# SCH_VELOS-R1_2025-07-28.net
KiCad netlist of a schematic drawn in EasyEDA
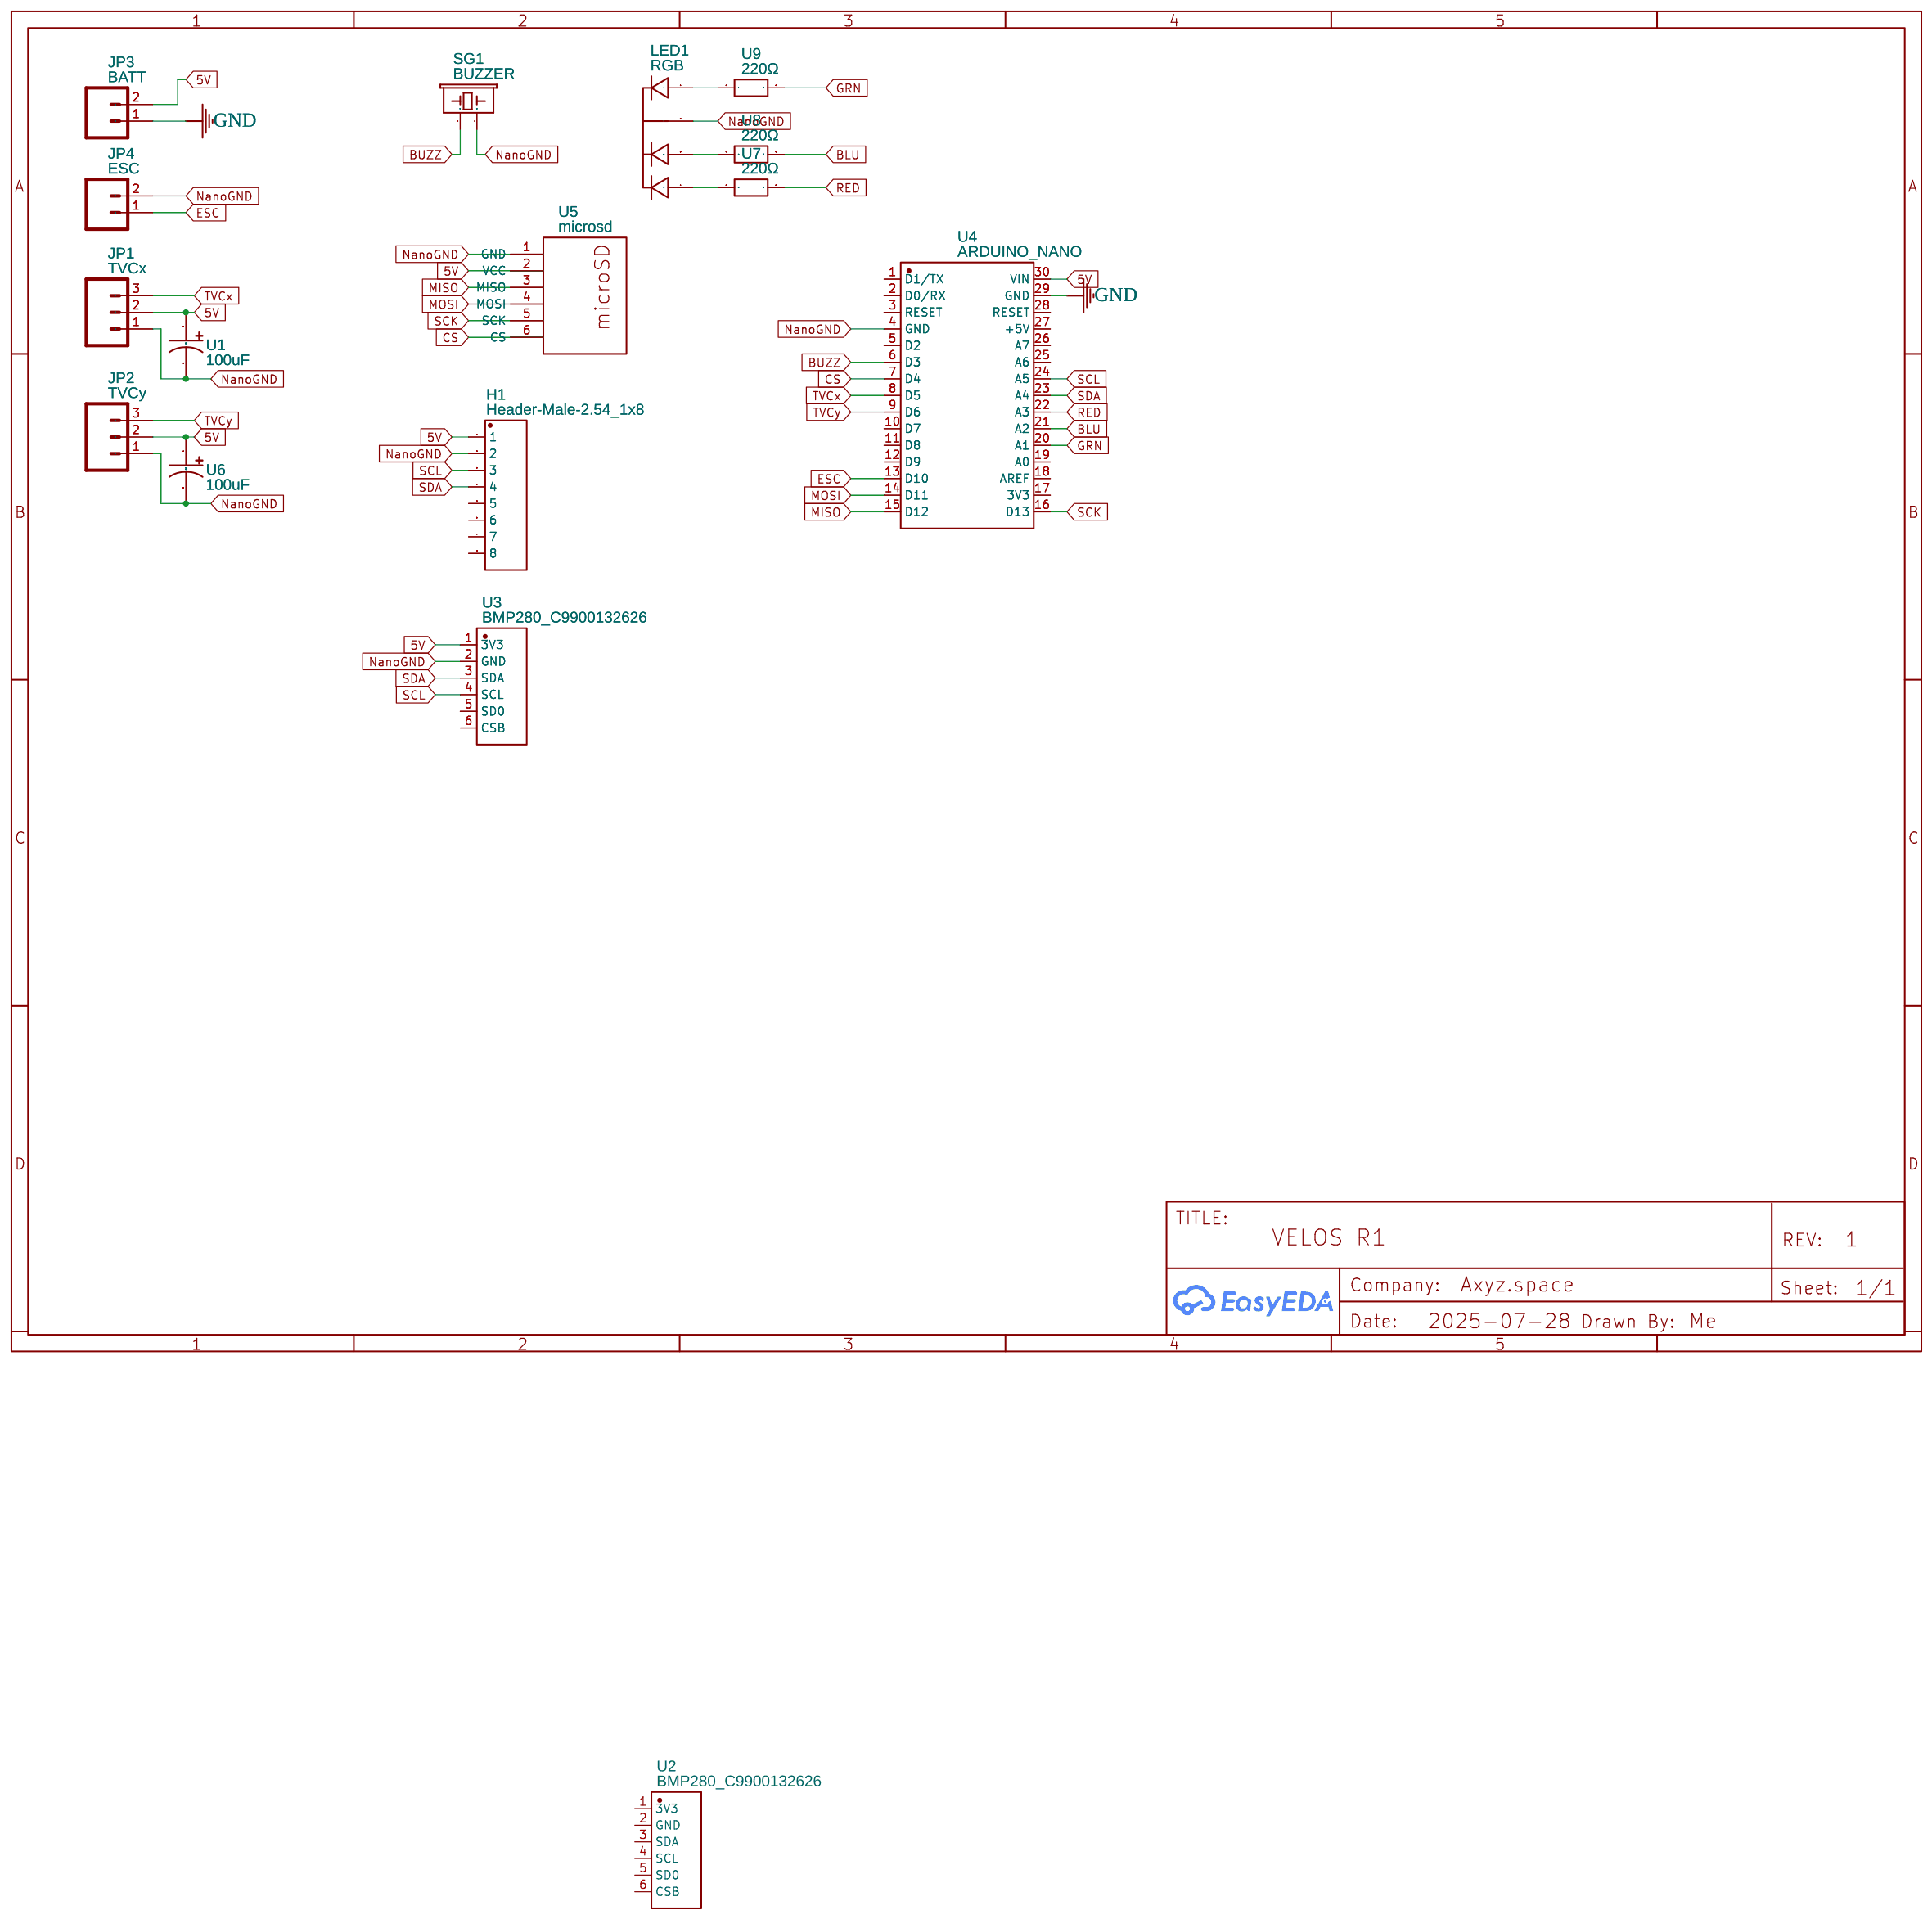
[diagram p0: schematic sheet]

(export (version "E")
  (design (tool "Eeschema 10.0.6"))
  (components
    (comp (ref "H1")
      (value "Header-Male-2.54_1x8")
      (fields (field (name "Manufacturer Part") "B-2100S08P-A110") (field (name "Manufacturer") "Ckmtw(灿科盟)"))
      (libsource (lib "") (part "Header-Male-2.54_1x8"))
    )
    (comp (ref "JP1") (value "TVCx") (libsource (lib "") (part "M03-SCREW-5MM")))
    (comp (ref "JP2") (value "TVCy") (libsource (lib "") (part "M03-SCREW-5MM")))
    (comp (ref "JP3") (value "BATT") (libsource (lib "") (part "M023.5MM")))
    (comp (ref "JP4") (value "ESC") (libsource (lib "") (part "M023.5MM")))
    (comp (ref "LED1")
      (value "RGB")
      (fields
        (field (name "Manufacturer Part") "TJ-L5FYTXHMCSLCRGB-A5")
        (field (name "Manufacturer") "TOGIALED(统佳)")
      )
      (libsource (lib "") (part "TJ-L5FYTXHMCSLCRGB-A5"))
    )
    (comp (ref "SG1") (value "BUZZER") (libsource (lib "") (part "BUZZER")))
    (comp (ref "U1")
      (value "100uF")
      (fields
        (field (name "Manufacturer Part") "35ZLH100MHFC(6.3X11)")
        (field (name "Manufacturer") "rubycon(红宝石)")
      )
      (libsource (lib "") (part "35ZLH100MHFC(6.3X11)"))
    )
    (comp (ref "U2")
      (value "BMP280_C9900132626")
      (fields (field (name "Manufacturer Part") "BMP280"))
      (libsource (lib "") (part "BMP280_C9900132626"))
    )
    (comp (ref "U3")
      (value "BMP280_C9900132626")
      (fields (field (name "Manufacturer Part") "BMP280"))
      (libsource (lib "") (part "BMP280_C9900132626"))
    )
    (comp (ref "U4") (value "ARDUINO_NANO") (libsource (lib "") (part "ARDUINO_NANO")))
    (comp (ref "U5") (value "microsd") (libsource (lib "") (part "microsd")))
    (comp (ref "U6")
      (value "100uF")
      (fields
        (field (name "Manufacturer Part") "35ZLH100MHFC(6.3X11)")
        (field (name "Manufacturer") "rubycon(红宝石)")
      )
      (libsource (lib "") (part "35ZLH100MHFC(6.3X11)"))
    )
    (comp (ref "U7")
      (value "220Ω")
      (fields
        (field (name "Manufacturer Part") "MBE04140C2200FC100")
        (field (name "Manufacturer") "VISHAY(威世)")
      )
      (libsource (lib "") (part "MBE04140C2200FC100"))
    )
    (comp (ref "U8")
      (value "220Ω")
      (fields
        (field (name "Manufacturer Part") "MBE04140C2200FC100")
        (field (name "Manufacturer") "VISHAY(威世)")
      )
      (libsource (lib "") (part "MBE04140C2200FC100"))
    )
    (comp (ref "U9")
      (value "220Ω")
      (fields
        (field (name "Manufacturer Part") "MBE04140C2200FC100")
        (field (name "Manufacturer") "VISHAY(威世)")
      )
      (libsource (lib "") (part "MBE04140C2200FC100"))
    )
  )
  (nets
    (net (code "1") (name "5V") (class "Default")
      (node (ref "H1") (pin "1") (pinfunction "1_1") (pintype "unspecified"))
      (node (ref "JP1") (pin "2") (pinfunction "2_2") (pintype "unspecified"))
      (node (ref "JP2") (pin "2") (pinfunction "2_2") (pintype "unspecified"))
      (node (ref "JP3") (pin "2") (pinfunction "2_2") (pintype "unspecified"))
      (node (ref "U1") (pin "1") (pinfunction "1_1") (pintype "unspecified"))
      (node (ref "U3") (pin "1") (pinfunction "3V3_1") (pintype "unspecified"))
      (node (ref "U4") (pin "30") (pinfunction "VIN_30") (pintype "unspecified"))
      (node (ref "U5") (pin "2") (pinfunction "VCC_2") (pintype "unspecified"))
      (node (ref "U6") (pin "1") (pinfunction "1_1") (pintype "unspecified"))
    )
    (net (code "2") (name "BLU") (class "Default")
      (node (ref "U4") (pin "21") (pinfunction "A2_21") (pintype "unspecified"))
      (node (ref "U8") (pin "2") (pinfunction "2_2") (pintype "unspecified"))
    )
    (net (code "3") (name "BUZZ") (class "Default")
      (node (ref "SG1") (pin "+") (pinfunction "1_+") (pintype "unspecified"))
      (node (ref "U4") (pin "6") (pinfunction "D3_6") (pintype "unspecified"))
    )
    (net (code "4") (name "CS") (class "Default")
      (node (ref "U4") (pin "7") (pinfunction "D4_7") (pintype "unspecified"))
      (node (ref "U5") (pin "6") (pinfunction "CS_6") (pintype "unspecified"))
    )
    (net (code "5") (name "ESC") (class "Default")
      (node (ref "JP4") (pin "1") (pinfunction "1_1") (pintype "unspecified"))
      (node (ref "U4") (pin "13") (pinfunction "D10_13") (pintype "unspecified"))
    )
    (net (code "6") (name "GND") (class "Default")
      (node (ref "JP3") (pin "1") (pinfunction "1_1") (pintype "unspecified"))
      (node (ref "U4") (pin "29") (pinfunction "GND_29") (pintype "unspecified"))
    )
    (net (code "7") (name "GRN") (class "Default")
      (node (ref "U4") (pin "20") (pinfunction "A1_20") (pintype "unspecified"))
      (node (ref "U9") (pin "2") (pinfunction "2_2") (pintype "unspecified"))
    )
    (net (code "8") (name "MISO") (class "Default")
      (node (ref "U4") (pin "15") (pinfunction "D12_15") (pintype "unspecified"))
      (node (ref "U5") (pin "3") (pinfunction "MISO_3") (pintype "unspecified"))
    )
    (net (code "9") (name "MOSI") (class "Default")
      (node (ref "U4") (pin "14") (pinfunction "D11_14") (pintype "unspecified"))
      (node (ref "U5") (pin "4") (pinfunction "MOSI_4") (pintype "unspecified"))
    )
    (net (code "10") (name "NanoGND") (class "Default")
      (node (ref "H1") (pin "2") (pinfunction "2_2") (pintype "unspecified"))
      (node (ref "JP1") (pin "1") (pinfunction "1_1") (pintype "unspecified"))
      (node (ref "JP2") (pin "1") (pinfunction "1_1") (pintype "unspecified"))
      (node (ref "JP4") (pin "2") (pinfunction "2_2") (pintype "unspecified"))
      (node (ref "LED1") (pin "2") (pinfunction "-_2") (pintype "unspecified"))
      (node (ref "SG1") (pin "-") (pinfunction "2_-") (pintype "unspecified"))
      (node (ref "U1") (pin "2") (pinfunction "2_2") (pintype "unspecified"))
      (node (ref "U3") (pin "2") (pinfunction "GND_2") (pintype "unspecified"))
      (node (ref "U4") (pin "4") (pinfunction "GND_4") (pintype "unspecified"))
      (node (ref "U5") (pin "1") (pinfunction "GND_1") (pintype "unspecified"))
      (node (ref "U6") (pin "2") (pinfunction "2_2") (pintype "unspecified"))
    )
    (net (code "11") (name "Net-(LED1-Pad1)") (class "Default")
      (node (ref "LED1") (pin "1") (pinfunction "1_1") (pintype "unspecified"))
      (node (ref "U9") (pin "1") (pinfunction "1_1") (pintype "unspecified"))
    )
    (net (code "12") (name "Net-(LED1-Pad3)") (class "Default")
      (node (ref "LED1") (pin "3") (pinfunction "3_3") (pintype "unspecified"))
      (node (ref "U8") (pin "1") (pinfunction "1_1") (pintype "unspecified"))
    )
    (net (code "13") (name "Net-(LED1-Pad4)") (class "Default")
      (node (ref "LED1") (pin "4") (pinfunction "4_4") (pintype "unspecified"))
      (node (ref "U7") (pin "1") (pinfunction "1_1") (pintype "unspecified"))
    )
    (net (code "14") (name "RED") (class "Default")
      (node (ref "U4") (pin "22") (pinfunction "A3_22") (pintype "unspecified"))
      (node (ref "U7") (pin "2") (pinfunction "2_2") (pintype "unspecified"))
    )
    (net (code "15") (name "SCK") (class "Default")
      (node (ref "U4") (pin "16") (pinfunction "D13_16") (pintype "unspecified"))
      (node (ref "U5") (pin "5") (pinfunction "SCK_5") (pintype "unspecified"))
    )
    (net (code "16") (name "SCL") (class "Default")
      (node (ref "H1") (pin "3") (pinfunction "3_3") (pintype "unspecified"))
      (node (ref "U3") (pin "4") (pinfunction "SCL_4") (pintype "unspecified"))
      (node (ref "U4") (pin "24") (pinfunction "A5_24") (pintype "unspecified"))
    )
    (net (code "17") (name "SDA") (class "Default")
      (node (ref "H1") (pin "4") (pinfunction "4_4") (pintype "unspecified"))
      (node (ref "U3") (pin "3") (pinfunction "SDA_3") (pintype "unspecified"))
      (node (ref "U4") (pin "23") (pinfunction "A4_23") (pintype "unspecified"))
    )
    (net (code "18") (name "TVCx") (class "Default")
      (node (ref "JP1") (pin "3") (pinfunction "3_3") (pintype "unspecified"))
      (node (ref "U4") (pin "8") (pinfunction "D5_8") (pintype "unspecified"))
    )
    (net (code "19") (name "TVCy") (class "Default")
      (node (ref "JP2") (pin "3") (pinfunction "3_3") (pintype "unspecified"))
      (node (ref "U4") (pin "9") (pinfunction "D6_9") (pintype "unspecified"))
    )
    (net (code "20") (name "unconnected-(H1-Pad5)") (class "Default")
      (node (ref "H1") (pin "5") (pinfunction "5_5") (pintype "unspecified"))
    )
    (net (code "21") (name "unconnected-(H1-Pad6)") (class "Default")
      (node (ref "H1") (pin "6") (pinfunction "6_6") (pintype "unspecified"))
    )
    (net (code "22") (name "unconnected-(H1-Pad7)") (class "Default")
      (node (ref "H1") (pin "7") (pinfunction "7_7") (pintype "unspecified"))
    )
    (net (code "23") (name "unconnected-(H1-Pad8)") (class "Default")
      (node (ref "H1") (pin "8") (pinfunction "8_8") (pintype "unspecified"))
    )
    (net (code "24") (name "unconnected-(U2-3V3-Pad1)") (class "Default")
      (node (ref "U2") (pin "1") (pinfunction "3V3_1") (pintype "unspecified"))
    )
    (net (code "25") (name "unconnected-(U2-CSB-Pad6)") (class "Default")
      (node (ref "U2") (pin "6") (pinfunction "CSB_6") (pintype "unspecified"))
    )
    (net (code "26") (name "unconnected-(U2-GND-Pad2)") (class "Default")
      (node (ref "U2") (pin "2") (pinfunction "GND_2") (pintype "unspecified"))
    )
    (net (code "27") (name "unconnected-(U2-SCL-Pad4)") (class "Default")
      (node (ref "U2") (pin "4") (pinfunction "SCL_4") (pintype "unspecified"))
    )
    (net (code "28") (name "unconnected-(U2-SD0-Pad5)") (class "Default")
      (node (ref "U2") (pin "5") (pinfunction "SD0_5") (pintype "unspecified"))
    )
    (net (code "29") (name "unconnected-(U2-SDA-Pad3)") (class "Default")
      (node (ref "U2") (pin "3") (pinfunction "SDA_3") (pintype "unspecified"))
    )
    (net (code "30") (name "unconnected-(U3-CSB-Pad6)") (class "Default")
      (node (ref "U3") (pin "6") (pinfunction "CSB_6") (pintype "unspecified"))
    )
    (net (code "31") (name "unconnected-(U3-SD0-Pad5)") (class "Default")
      (node (ref "U3") (pin "5") (pinfunction "SD0_5") (pintype "unspecified"))
    )
    (net (code "32") (name "unconnected-(U4-+5V-Pad27)") (class "Default")
      (node (ref "U4") (pin "27") (pinfunction "+5V_27") (pintype "unspecified"))
    )
    (net (code "33") (name "unconnected-(U4-3V3-Pad17)") (class "Default")
      (node (ref "U4") (pin "17") (pinfunction "3V3_17") (pintype "unspecified"))
    )
    (net (code "34") (name "unconnected-(U4-A0-Pad19)") (class "Default")
      (node (ref "U4") (pin "19") (pinfunction "A0_19") (pintype "unspecified"))
    )
    (net (code "35") (name "unconnected-(U4-A6-Pad25)") (class "Default")
      (node (ref "U4") (pin "25") (pinfunction "A6_25") (pintype "unspecified"))
    )
    (net (code "36") (name "unconnected-(U4-A7-Pad26)") (class "Default")
      (node (ref "U4") (pin "26") (pinfunction "A7_26") (pintype "unspecified"))
    )
    (net (code "37") (name "unconnected-(U4-AREF-Pad18)") (class "Default")
      (node (ref "U4") (pin "18") (pinfunction "AREF_18") (pintype "unspecified"))
    )
    (net (code "38") (name "unconnected-(U4-D0{slash}RX-Pad2)") (class "Default")
      (node (ref "U4") (pin "2") (pinfunction "D0/RX_2") (pintype "unspecified"))
    )
    (net (code "39") (name "unconnected-(U4-D1{slash}TX-Pad1)") (class "Default")
      (node (ref "U4") (pin "1") (pinfunction "D1/TX_1") (pintype "unspecified"))
    )
    (net (code "40") (name "unconnected-(U4-D2-Pad5)") (class "Default")
      (node (ref "U4") (pin "5") (pinfunction "D2_5") (pintype "unspecified"))
    )
    (net (code "41") (name "unconnected-(U4-D7-Pad10)") (class "Default")
      (node (ref "U4") (pin "10") (pinfunction "D7_10") (pintype "unspecified"))
    )
    (net (code "42") (name "unconnected-(U4-D8-Pad11)") (class "Default")
      (node (ref "U4") (pin "11") (pinfunction "D8_11") (pintype "unspecified"))
    )
    (net (code "43") (name "unconnected-(U4-D9-Pad12)") (class "Default")
      (node (ref "U4") (pin "12") (pinfunction "D9_12") (pintype "unspecified"))
    )
    (net (code "44") (name "unconnected-(U4-RESET-Pad3)") (class "Default")
      (node (ref "U4") (pin "3") (pinfunction "RESET_3") (pintype "unspecified"))
    )
    (net (code "45") (name "unconnected-(U4-RESET-Pad28)") (class "Default")
      (node (ref "U4") (pin "28") (pinfunction "RESET_28") (pintype "unspecified"))
    )
  )
)
